# switch_b_board.net
KiCad netlist of a schematic drawn in EAGLE
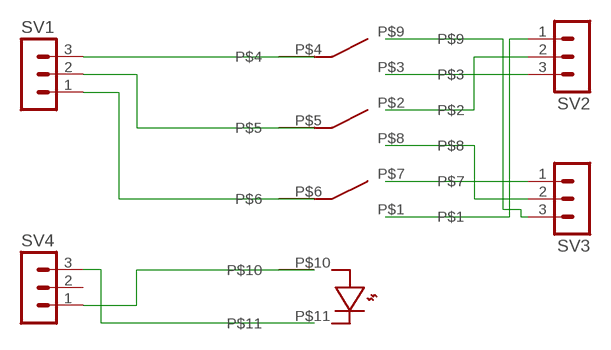
[diagram p0: schematic, sheet 1]

(export (version "E")
  (design (tool "Eeschema 10.0.6"))
  (components
    (comp (ref "SV1")
      (value "MA03-1")
      (footprint "eagle-import:MA03-1")
      (libsource (lib "eagle-import") (part "MA03-1"))
    )
    (comp (ref "SV2")
      (value "MA03-1")
      (footprint "eagle-import:MA03-1")
      (libsource (lib "eagle-import") (part "MA03-1"))
    )
    (comp (ref "SV3")
      (value "MA03-1")
      (footprint "eagle-import:MA03-1")
      (libsource (lib "eagle-import") (part "MA03-1"))
    )
    (comp (ref "SV4")
      (value "MA03-1")
      (footprint "eagle-import:MA03-1")
      (libsource (lib "eagle-import") (part "MA03-1"))
    )
    (comp (ref "U$1")
      (value "FOOT_SWITCH")
      (footprint "eagle-import:FOOT_SWITCH")
      (libsource (lib "eagle-import") (part "FOOT_SWITCH"))
    )
  )
  (nets
    (net (code "1") (name "Net-(SV1-Pad1)") (class "Default")
      (node (ref "SV1") (pin "1") (pinfunction "1_1") (pintype "passive"))
      (node (ref "U$1") (pin "P$6") (pinfunction "P$6_P$6") (pintype "bidirectional"))
    )
    (net (code "2") (name "Net-(SV1-Pad2)") (class "Default")
      (node (ref "SV1") (pin "2") (pinfunction "2_2") (pintype "passive"))
      (node (ref "U$1") (pin "P$5") (pinfunction "P$5_P$5") (pintype "bidirectional"))
    )
    (net (code "3") (name "Net-(SV1-Pad3)") (class "Default")
      (node (ref "SV1") (pin "3") (pinfunction "3_3") (pintype "passive"))
      (node (ref "U$1") (pin "P$4") (pinfunction "P$4_P$4") (pintype "bidirectional"))
    )
    (net (code "4") (name "Net-(SV2-Pad1)") (class "Default")
      (node (ref "SV2") (pin "1") (pinfunction "1_1") (pintype "passive"))
      (node (ref "U$1") (pin "P$1") (pinfunction "P$1_P$1") (pintype "bidirectional"))
    )
    (net (code "5") (name "Net-(SV2-Pad2)") (class "Default")
      (node (ref "SV2") (pin "2") (pinfunction "2_2") (pintype "passive"))
      (node (ref "U$1") (pin "P$2") (pinfunction "P$2_P$2") (pintype "bidirectional"))
    )
    (net (code "6") (name "Net-(SV2-Pad3)") (class "Default")
      (node (ref "SV2") (pin "3") (pinfunction "3_3") (pintype "passive"))
      (node (ref "U$1") (pin "P$3") (pinfunction "P$3_P$3") (pintype "bidirectional"))
    )
    (net (code "7") (name "Net-(SV3-Pad1)") (class "Default")
      (node (ref "SV3") (pin "1") (pinfunction "1_1") (pintype "passive"))
      (node (ref "U$1") (pin "P$7") (pinfunction "P$7_P$7") (pintype "bidirectional"))
    )
    (net (code "8") (name "Net-(SV3-Pad2)") (class "Default")
      (node (ref "SV3") (pin "2") (pinfunction "2_2") (pintype "passive"))
      (node (ref "U$1") (pin "P$8") (pinfunction "P$8_P$8") (pintype "bidirectional"))
    )
    (net (code "9") (name "Net-(SV3-Pad3)") (class "Default")
      (node (ref "SV3") (pin "3") (pinfunction "3_3") (pintype "passive"))
      (node (ref "U$1") (pin "P$9") (pinfunction "P$9_P$9") (pintype "bidirectional"))
    )
    (net (code "10") (name "Net-(SV4-Pad1)") (class "Default")
      (node (ref "SV4") (pin "1") (pinfunction "1_1") (pintype "passive"))
      (node (ref "U$1") (pin "P$10") (pinfunction "P$10_P$10") (pintype "bidirectional"))
    )
    (net (code "11") (name "Net-(SV4-Pad3)") (class "Default")
      (node (ref "SV4") (pin "3") (pinfunction "3_3") (pintype "passive"))
      (node (ref "U$1") (pin "P$11") (pinfunction "P$11_P$11") (pintype "bidirectional"))
    )
    (net (code "12") (name "unconnected-(SV4-Pad2)") (class "Default")
      (node (ref "SV4") (pin "2") (pinfunction "2_2") (pintype "passive"))
    )
  )
)
